# Sheet1.net
KiCad netlist of a schematic drawn in Altium Designer
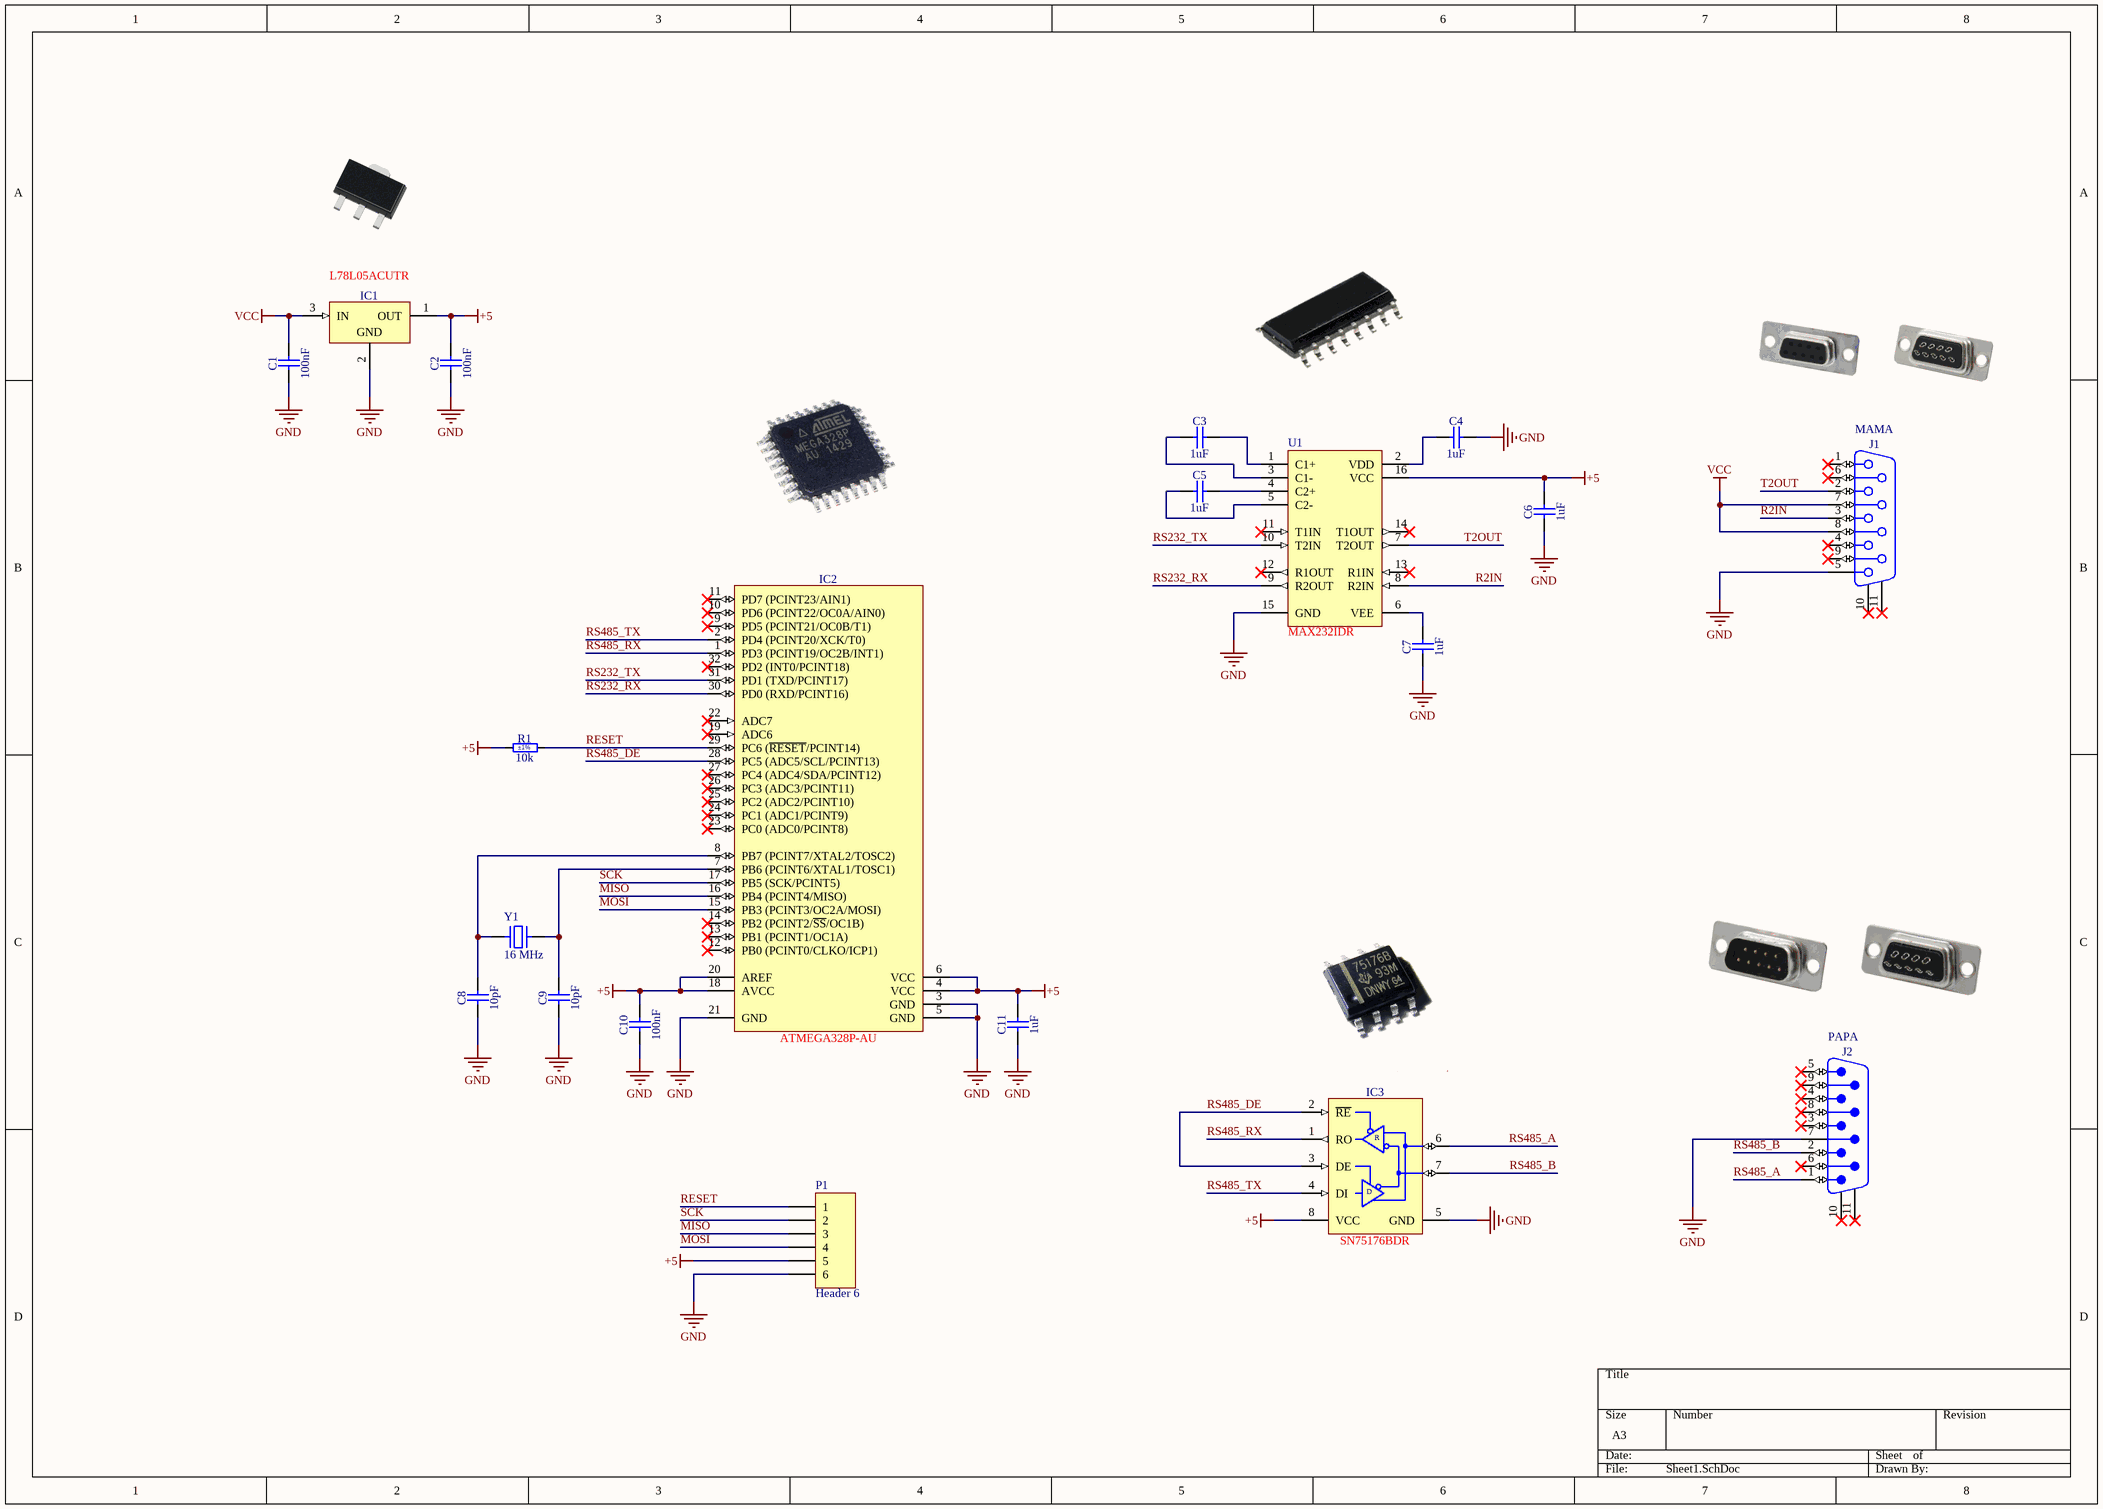
[diagram p0: Sheet1.SchDoc]

(export (version "E")
  (design (tool "Eeschema 10.0.6"))
  (components
    (comp (ref "C1")
      (value "100nF")
      (footprint "CAPC2012X135N")
      (description "Non-polarised capacitor")
      (fields
        (field (name "PART NUMBER") "CC0805_100NF_50V_10%_X7R")
        (field (name "VOLTAGE") "50V")
        (field (name "AUTHOR") "CERN DEM JLC")
      )
      (libsource (lib "Capacitors") (part "Capacitor - non polarized"))
    )
    (comp (ref "C2")
      (value "100nF")
      (footprint "CAPC2012X135N")
      (description "Non-polarised capacitor")
      (fields
        (field (name "PART NUMBER") "CC0805_100NF_50V_10%_X7R")
        (field (name "VOLTAGE") "50V")
        (field (name "AUTHOR") "CERN DEM JLC")
      )
      (libsource (lib "Capacitors") (part "Capacitor - non polarized"))
    )
    (comp (ref "C3")
      (value "1uF")
      (footprint "CAPC2012X140N")
      (description "Non-polarised capacitor")
      (fields
        (field (name "PART NUMBER") "CC0805_1UF_25V_10%_X7R")
        (field (name "VOLTAGE") "25V")
        (field (name "AUTHOR") "CERN DEM JLC")
      )
      (libsource (lib "Capacitors") (part "Capacitor - non polarized"))
    )
    (comp (ref "C4")
      (value "1uF")
      (footprint "CAPC2012X140N")
      (description "Non-polarised capacitor")
      (fields
        (field (name "PART NUMBER") "CC0805_1UF_25V_10%_X7R")
        (field (name "VOLTAGE") "25V")
        (field (name "AUTHOR") "CERN DEM JLC")
      )
      (libsource (lib "Capacitors") (part "Capacitor - non polarized"))
    )
    (comp (ref "C5")
      (value "1uF")
      (footprint "CAPC2012X140N")
      (description "Non-polarised capacitor")
      (fields
        (field (name "PART NUMBER") "CC0805_1UF_25V_10%_X7R")
        (field (name "VOLTAGE") "25V")
        (field (name "AUTHOR") "CERN DEM JLC")
      )
      (libsource (lib "Capacitors") (part "Capacitor - non polarized"))
    )
    (comp (ref "C6")
      (value "1uF")
      (footprint "CAPC2012X140N")
      (description "Non-polarised capacitor")
      (fields
        (field (name "PART NUMBER") "CC0805_1UF_25V_10%_X7R")
        (field (name "VOLTAGE") "25V")
        (field (name "AUTHOR") "CERN DEM JLC")
      )
      (libsource (lib "Capacitors") (part "Capacitor - non polarized"))
    )
    (comp (ref "C7")
      (value "1uF")
      (footprint "CAPC2012X140N")
      (description "Non-polarised capacitor")
      (fields
        (field (name "PART NUMBER") "CC0805_1UF_25V_10%_X7R")
        (field (name "VOLTAGE") "25V")
        (field (name "AUTHOR") "CERN DEM JLC")
      )
      (libsource (lib "Capacitors") (part "Capacitor - non polarized"))
    )
    (comp (ref "C8")
      (value "10pF")
      (footprint "CAPC2012X135N")
      (description "Non-polarised capacitor")
      (fields
        (field (name "PART NUMBER") "CC0805_10PF_50V_1%_NP0")
        (field (name "VOLTAGE") "50V")
        (field (name "AUTHOR") "CERN DEM MR")
      )
      (libsource (lib "Capacitors") (part "Capacitor - non polarized"))
    )
    (comp (ref "C9")
      (value "10pF")
      (footprint "CAPC2012X135N")
      (description "Non-polarised capacitor")
      (fields
        (field (name "PART NUMBER") "CC0805_10PF_50V_1%_NP0")
        (field (name "VOLTAGE") "50V")
        (field (name "AUTHOR") "CERN DEM MR")
      )
      (libsource (lib "Capacitors") (part "Capacitor - non polarized"))
    )
    (comp (ref "C10")
      (value "100nF")
      (footprint "CAPC2012X135N")
      (description "Non-polarised capacitor")
      (fields
        (field (name "PART NUMBER") "CC0805_100NF_50V_10%_X7R")
        (field (name "VOLTAGE") "50V")
        (field (name "AUTHOR") "CERN DEM JLC")
      )
      (libsource (lib "Capacitors") (part "Capacitor - non polarized"))
    )
    (comp (ref "C11")
      (value "1uF")
      (footprint "CAPC2012X140N")
      (description "Non-polarised capacitor")
      (fields
        (field (name "PART NUMBER") "CC0805_1UF_25V_10%_X7R")
        (field (name "VOLTAGE") "25V")
        (field (name "AUTHOR") "CERN DEM JLC")
      )
      (libsource (lib "Capacitors") (part "Capacitor - non polarized"))
    )
    (comp (ref "IC1")
      (value "L78L05ACUTR")
      (footprint "SOT89")
      (fields (field (name "MANUFACTURER") "ST MICROELECTRONICS") (field (name "AUTHOR") "CERN DEM JLC"))
      (libsource (lib "ICs And Semiconductors") (part "REG3 1OUT-2GND-3IN"))
    )
    (comp (ref "IC2")
      (value "ATMEGA328P-AU")
      (footprint "QFP80P900X900X120-32N")
      (description "8-bit AVR Microcontroller, 32KB Flash, 1KB EEPROM, 2KB SRAM, 32-Pin TQFP")
      (fields (field (name "MANUFACTURER") "ATMEL") (field (name "AUTHOR") "CERN DEM JLC"))
      (libsource (lib "ICs And Semiconductors") (part "ATMEGA328P-AU"))
    )
    (comp (ref "IC3")
      (value "SN75176BDR")
      (footprint "SOIC127P600X175-8N")
      (description "transceiver 4.75V~5.25V 1/1 SOIC-8_150mil RS-485/RS-422 ICs ROHS")
      (fields (field (name "AUTHOR") "CERN DEM JLC"))
      (libsource (lib "ICs And Semiconductors") (part "MAX3485"))
    )
    (comp (ref "J1")
      (value "D-Sub 9F")
      (footprint "D-Sub-9-pin:D-Sub")
      (description "Connector D-sub 9 Female")
      (fields
        (field (name "PART NUMBER") "HARTING_09 67 009 4754")
        (field (name "MANUFACTURER") "HARTING")
        (field (name "AUTHOR") "CERN DEM BC")
      )
      (libsource (lib "Connectors") (part "Connector D-sub 9 Female"))
    )
    (comp (ref "J2")
      (value "D-Sub 9M")
      (footprint "D-Sub-9-pin:D-Sub")
      (description "Connector D-sub 9 Male")
      (fields
        (field (name "PART NUMBER") "HARTING_09 66 162 6817")
        (field (name "MANUFACTURER") "HARTING")
        (field (name "AUTHOR") "CERN DEM HF")
      )
      (libsource (lib "Connectors") (part "Connector D-sub 9 Male"))
    )
    (comp (ref "P1")
      (value "Header 6")
      (footprint "HDR1X6")
      (description "Header, 6-Pin")
      (fields (field (name "PUBLISHER") "Altium Limited"))
      (libsource (lib "Miscellaneous Connectors") (part "Header 6"))
    )
    (comp (ref "R1")
      (value "10k")
      (footprint "RESC2012X60N")
      (description "Resistor - 1%")
      (fields
        (field (name "TOLERANCE") "±1%")
        (field (name "PART NUMBER") "R0805_10K_1%_0.125W_100PPM")
        (field (name "POWER") "0.125W")
        (field (name "AUTHOR") "CERN DEM JLC")
      )
      (libsource (lib "Resistors") (part "Resistor - 1%"))
    )
    (comp (ref "U1")
      (value "MAX232IDR")
      (footprint "SOIC-16 9.9X3.9MM P1.27MM")
      (description "120Kbps 4.5V~5.5V transceiver 2/2 SOIC-16 RS232 ICs ROHS")
      (libsource (lib "Chip") (part "MAX232 (SMD)"))
    )
    (comp (ref "Y1")
      (value "16 MHz")
      (footprint "NDK NX5032GA")
      (description "CRYSTAL 16.0000MHZ 8PF SMD")
      (fields
        (field (name "PART NUMBER") "NX5032GA-16MHZ-STD-CSK-4")
        (field (name "MANUFACTURER") "NDK America, Inc.")
      )
      (libsource (lib "altium_library") (part "NDK Crystal NX5032GA"))
    )
  )
  (nets
    (net (code "1") (name "+5") (class "Default")
      (node (ref "C10") (pin "2") (pinfunction "2_2") (pintype "passive"))
      (node (ref "C11") (pin "2") (pinfunction "2_2") (pintype "passive"))
      (node (ref "C2") (pin "2") (pinfunction "2_2") (pintype "passive"))
      (node (ref "C6") (pin "2") (pinfunction "2_2") (pintype "passive"))
      (node (ref "IC1") (pin "1") (pinfunction "OUT_1") (pintype "power_in"))
      (node (ref "IC2") (pin "18") (pinfunction "AVCC_18") (pintype "power_in"))
      (node (ref "IC2") (pin "20") (pinfunction "AREF_20") (pintype "passive"))
      (node (ref "IC2") (pin "4") (pinfunction "VCC_4") (pintype "power_in"))
      (node (ref "IC2") (pin "6") (pinfunction "VCC_6") (pintype "power_in"))
      (node (ref "IC3") (pin "8") (pinfunction "VCC_8") (pintype "power_in"))
      (node (ref "P1") (pin "5") (pinfunction "5_5") (pintype "passive"))
      (node (ref "R1") (pin "1") (pinfunction "1_1") (pintype "passive"))
      (node (ref "U1") (pin "16") (pinfunction "VCC_16") (pintype "power_in"))
    )
    (net (code "2") (name "/MISO") (class "Default")
      (node (ref "IC2") (pin "16") (pinfunction "PB4_(PCINT4/MISO)_16") (pintype "bidirectional"))
      (node (ref "P1") (pin "3") (pinfunction "3_3") (pintype "passive"))
    )
    (net (code "3") (name "/MOSI") (class "Default")
      (node (ref "IC2") (pin "15") (pinfunction "PB3_(PCINT3/OC2A/MOSI)_15") (pintype "bidirectional"))
      (node (ref "P1") (pin "4") (pinfunction "4_4") (pintype "passive"))
    )
    (net (code "4") (name "/R2IN") (class "Default")
      (node (ref "J1") (pin "3") (pinfunction "3_3") (pintype "bidirectional"))
      (node (ref "U1") (pin "8") (pinfunction "R2IN_8") (pintype "input"))
    )
    (net (code "5") (name "/RESET") (class "Default")
      (node (ref "IC2") (pin "29") (pinfunction "PC6_(~{RESET}/PCINT14)_29") (pintype "bidirectional"))
      (node (ref "P1") (pin "1") (pinfunction "1_1") (pintype "passive"))
      (node (ref "R1") (pin "2") (pinfunction "2_2") (pintype "passive"))
    )
    (net (code "6") (name "/RS232_RX") (class "Default")
      (node (ref "IC2") (pin "30") (pinfunction "PD0_(RXD/PCINT16)_30") (pintype "bidirectional"))
      (node (ref "U1") (pin "9") (pinfunction "R2OUT_9") (pintype "output"))
    )
    (net (code "7") (name "/RS232_TX") (class "Default")
      (node (ref "IC2") (pin "31") (pinfunction "PD1_(TXD/PCINT17)_31") (pintype "bidirectional"))
      (node (ref "U1") (pin "10") (pinfunction "T2IN_10") (pintype "input"))
    )
    (net (code "8") (name "/RS485_A") (class "Default")
      (node (ref "IC3") (pin "6") (pinfunction "A_6") (pintype "bidirectional"))
      (node (ref "J2") (pin "1") (pinfunction "1_1") (pintype "bidirectional"))
    )
    (net (code "9") (name "/RS485_B") (class "Default")
      (node (ref "IC3") (pin "7") (pinfunction "B_7") (pintype "bidirectional"))
      (node (ref "J2") (pin "2") (pinfunction "2_2") (pintype "bidirectional"))
    )
    (net (code "10") (name "/RS485_DE") (class "Default")
      (node (ref "IC2") (pin "28") (pinfunction "PC5_(ADC5/SCL/PCINT13)_28") (pintype "bidirectional"))
      (node (ref "IC3") (pin "2") (pinfunction "~{RE}_2") (pintype "input"))
      (node (ref "IC3") (pin "3") (pinfunction "DE_3") (pintype "input"))
    )
    (net (code "11") (name "/RS485_RX") (class "Default")
      (node (ref "IC2") (pin "1") (pinfunction "PD3_(PCINT19/OC2B/INT1)_1") (pintype "bidirectional"))
      (node (ref "IC3") (pin "1") (pinfunction "RO_1") (pintype "output"))
    )
    (net (code "12") (name "/RS485_TX") (class "Default")
      (node (ref "IC2") (pin "2") (pinfunction "PD4_(PCINT20/XCK/T0)_2") (pintype "bidirectional"))
      (node (ref "IC3") (pin "4") (pinfunction "DI_4") (pintype "input"))
    )
    (net (code "13") (name "/SCK") (class "Default")
      (node (ref "IC2") (pin "17") (pinfunction "PB5_(SCK/PCINT5)_17") (pintype "bidirectional"))
      (node (ref "P1") (pin "2") (pinfunction "2_2") (pintype "passive"))
    )
    (net (code "14") (name "/T2OUT") (class "Default")
      (node (ref "J1") (pin "2") (pinfunction "2_2") (pintype "bidirectional"))
      (node (ref "U1") (pin "7") (pinfunction "T2OUT_7") (pintype "output"))
    )
    (net (code "15") (name "GND") (class "Default")
      (node (ref "C1") (pin "1") (pinfunction "1_1") (pintype "passive"))
      (node (ref "C10") (pin "1") (pinfunction "1_1") (pintype "passive"))
      (node (ref "C11") (pin "1") (pinfunction "1_1") (pintype "passive"))
      (node (ref "C2") (pin "1") (pinfunction "1_1") (pintype "passive"))
      (node (ref "C4") (pin "2") (pinfunction "2_2") (pintype "passive"))
      (node (ref "C6") (pin "1") (pinfunction "1_1") (pintype "passive"))
      (node (ref "C7") (pin "1") (pinfunction "1_1") (pintype "passive"))
      (node (ref "C8") (pin "1") (pinfunction "1_1") (pintype "passive"))
      (node (ref "C9") (pin "1") (pinfunction "1_1") (pintype "passive"))
      (node (ref "IC1") (pin "2") (pinfunction "GND_2") (pintype "power_in"))
      (node (ref "IC2") (pin "21") (pinfunction "GND_21") (pintype "power_in"))
      (node (ref "IC2") (pin "3") (pinfunction "GND_3") (pintype "power_in"))
      (node (ref "IC2") (pin "5") (pinfunction "GND_5") (pintype "power_in"))
      (node (ref "IC3") (pin "5") (pinfunction "GND_5") (pintype "power_in"))
      (node (ref "J1") (pin "5") (pinfunction "5_5") (pintype "power_in"))
      (node (ref "J2") (pin "7") (pinfunction "7_7") (pintype "passive"))
      (node (ref "P1") (pin "6") (pinfunction "6_6") (pintype "passive"))
      (node (ref "U1") (pin "15") (pinfunction "GND_15") (pintype "power_in"))
    )
    (net (code "16") (name "Net-(IC2-PB6_(PCINT6{slash}XTAL1{slash}TOSC1))") (class "Default")
      (node (ref "C9") (pin "2") (pinfunction "2_2") (pintype "passive"))
      (node (ref "IC2") (pin "7") (pinfunction "PB6_(PCINT6/XTAL1/TOSC1)_7") (pintype "bidirectional"))
      (node (ref "Y1") (pin "1") (pinfunction "1_1") (pintype "passive"))
    )
    (net (code "17") (name "Net-(IC2-PB7_(PCINT7{slash}XTAL2{slash}TOSC2))") (class "Default")
      (node (ref "C8") (pin "2") (pinfunction "2_2") (pintype "passive"))
      (node (ref "IC2") (pin "8") (pinfunction "PB7_(PCINT7/XTAL2/TOSC2)_8") (pintype "bidirectional"))
      (node (ref "Y1") (pin "2") (pinfunction "2_2") (pintype "passive"))
    )
    (net (code "18") (name "Net-(U1-C1+)") (class "Default")
      (node (ref "C3") (pin "2") (pinfunction "2_2") (pintype "passive"))
      (node (ref "U1") (pin "1") (pinfunction "C1+_1") (pintype "passive"))
    )
    (net (code "19") (name "Net-(U1-C1-)") (class "Default")
      (node (ref "C3") (pin "1") (pinfunction "1_1") (pintype "passive"))
      (node (ref "U1") (pin "3") (pinfunction "C1-_3") (pintype "passive"))
    )
    (net (code "20") (name "Net-(U1-C2+)") (class "Default")
      (node (ref "C5") (pin "2") (pinfunction "2_2") (pintype "passive"))
      (node (ref "U1") (pin "4") (pinfunction "C2+_4") (pintype "passive"))
    )
    (net (code "21") (name "Net-(U1-C2-)") (class "Default")
      (node (ref "C5") (pin "1") (pinfunction "1_1") (pintype "passive"))
      (node (ref "U1") (pin "5") (pinfunction "C2-_5") (pintype "passive"))
    )
    (net (code "22") (name "Net-(U1-VDD)") (class "Default")
      (node (ref "C4") (pin "1") (pinfunction "1_1") (pintype "passive"))
      (node (ref "U1") (pin "2") (pinfunction "VDD_2") (pintype "power_in"))
    )
    (net (code "23") (name "Net-(U1-VEE)") (class "Default")
      (node (ref "C7") (pin "2") (pinfunction "2_2") (pintype "passive"))
      (node (ref "U1") (pin "6") (pinfunction "VEE_6") (pintype "power_in"))
    )
    (net (code "24") (name "VCC") (class "Default")
      (node (ref "C1") (pin "2") (pinfunction "2_2") (pintype "passive"))
      (node (ref "IC1") (pin "3") (pinfunction "IN_3") (pintype "input"))
      (node (ref "J1") (pin "7") (pinfunction "7_7") (pintype "bidirectional"))
      (node (ref "J1") (pin "8") (pinfunction "8_8") (pintype "bidirectional"))
    )
    (net (code "25") (name "unconnected-(IC2-ADC6-Pad19)") (class "Default")
      (node (ref "IC2") (pin "19") (pinfunction "ADC6_19") (pintype "input+no_connect"))
    )
    (net (code "26") (name "unconnected-(IC2-ADC7-Pad22)") (class "Default")
      (node (ref "IC2") (pin "22") (pinfunction "ADC7_22") (pintype "input+no_connect"))
    )
    (net (code "27") (name "unconnected-(IC2-PB0_(PCINT0{slash}CLKO{slash}ICP1)-Pad12)") (class "Default")
      (node (ref "IC2") (pin "12") (pinfunction "PB0_(PCINT0/CLKO/ICP1)_12") (pintype "bidirectional+no_connect"))
    )
    (net (code "28") (name "unconnected-(IC2-PB1_(PCINT1{slash}OC1A)-Pad13)") (class "Default")
      (node (ref "IC2") (pin "13") (pinfunction "PB1_(PCINT1/OC1A)_13") (pintype "bidirectional+no_connect"))
    )
    (net (code "29") (name "unconnected-(IC2-PB2_(PCINT2{slash}~{SS}{slash}OC1B)-Pad14)") (class "Default")
      (node (ref "IC2") (pin "14") (pinfunction "PB2_(PCINT2/~{SS}/OC1B)_14") (pintype "bidirectional+no_connect"))
    )
    (net (code "30") (name "unconnected-(IC2-PC0_(ADC0{slash}PCINT8)-Pad23)") (class "Default")
      (node (ref "IC2") (pin "23") (pinfunction "PC0_(ADC0/PCINT8)_23") (pintype "bidirectional+no_connect"))
    )
    (net (code "31") (name "unconnected-(IC2-PC1_(ADC1{slash}PCINT9)-Pad24)") (class "Default")
      (node (ref "IC2") (pin "24") (pinfunction "PC1_(ADC1/PCINT9)_24") (pintype "bidirectional+no_connect"))
    )
    (net (code "32") (name "unconnected-(IC2-PC2_(ADC2{slash}PCINT10)-Pad25)") (class "Default")
      (node (ref "IC2") (pin "25") (pinfunction "PC2_(ADC2/PCINT10)_25") (pintype "bidirectional+no_connect"))
    )
    (net (code "33") (name "unconnected-(IC2-PC3_(ADC3{slash}PCINT11)-Pad26)") (class "Default")
      (node (ref "IC2") (pin "26") (pinfunction "PC3_(ADC3/PCINT11)_26") (pintype "bidirectional+no_connect"))
    )
    (net (code "34") (name "unconnected-(IC2-PC4_(ADC4{slash}SDA{slash}PCINT12)-Pad27)") (class "Default")
      (node (ref "IC2") (pin "27") (pinfunction "PC4_(ADC4/SDA/PCINT12)_27") (pintype "bidirectional+no_connect"))
    )
    (net (code "35") (name "unconnected-(IC2-PD2_(INT0{slash}PCINT18)-Pad32)") (class "Default")
      (node (ref "IC2") (pin "32") (pinfunction "PD2_(INT0/PCINT18)_32") (pintype "bidirectional+no_connect"))
    )
    (net (code "36") (name "unconnected-(IC2-PD5_(PCINT21{slash}OC0B{slash}T1)-Pad9)") (class "Default")
      (node (ref "IC2") (pin "9") (pinfunction "PD5_(PCINT21/OC0B/T1)_9") (pintype "bidirectional+no_connect"))
    )
    (net (code "37") (name "unconnected-(IC2-PD6_(PCINT22{slash}OC0A{slash}AIN0)-Pad10)") (class "Default")
      (node (ref "IC2") (pin "10") (pinfunction "PD6_(PCINT22/OC0A/AIN0)_10") (pintype "bidirectional+no_connect"))
    )
    (net (code "38") (name "unconnected-(IC2-PD7_(PCINT23{slash}AIN1)-Pad11)") (class "Default")
      (node (ref "IC2") (pin "11") (pinfunction "PD7_(PCINT23/AIN1)_11") (pintype "bidirectional+no_connect"))
    )
    (net (code "39") (name "unconnected-(J1-Pad1)") (class "Default")
      (node (ref "J1") (pin "1") (pinfunction "1_1") (pintype "bidirectional+no_connect"))
    )
    (net (code "40") (name "unconnected-(J1-Pad4)") (class "Default")
      (node (ref "J1") (pin "4") (pinfunction "4_4") (pintype "bidirectional+no_connect"))
    )
    (net (code "41") (name "unconnected-(J1-Pad6)") (class "Default")
      (node (ref "J1") (pin "6") (pinfunction "6_6") (pintype "bidirectional+no_connect"))
    )
    (net (code "42") (name "unconnected-(J1-Pad9)") (class "Default")
      (node (ref "J1") (pin "9") (pinfunction "9_9") (pintype "bidirectional+no_connect"))
    )
    (net (code "43") (name "unconnected-(J1-Pad10)") (class "Default")
      (node (ref "J1") (pin "10") (pinfunction "10_10") (pintype "passive+no_connect"))
    )
    (net (code "44") (name "unconnected-(J1-Pad11)") (class "Default")
      (node (ref "J1") (pin "11") (pinfunction "11_11") (pintype "passive+no_connect"))
    )
    (net (code "45") (name "unconnected-(J2-Pad3)") (class "Default")
      (node (ref "J2") (pin "3") (pinfunction "3_3") (pintype "bidirectional+no_connect"))
    )
    (net (code "46") (name "unconnected-(J2-Pad4)") (class "Default")
      (node (ref "J2") (pin "4") (pinfunction "4_4") (pintype "bidirectional+no_connect"))
    )
    (net (code "47") (name "unconnected-(J2-Pad5)") (class "Default")
      (node (ref "J2") (pin "5") (pinfunction "5_5") (pintype "bidirectional+no_connect"))
    )
    (net (code "48") (name "unconnected-(J2-Pad6)") (class "Default")
      (node (ref "J2") (pin "6") (pinfunction "6_6") (pintype "bidirectional+no_connect"))
    )
    (net (code "49") (name "unconnected-(J2-Pad8)") (class "Default")
      (node (ref "J2") (pin "8") (pinfunction "8_8") (pintype "bidirectional+no_connect"))
    )
    (net (code "50") (name "unconnected-(J2-Pad9)") (class "Default")
      (node (ref "J2") (pin "9") (pinfunction "9_9") (pintype "bidirectional+no_connect"))
    )
    (net (code "51") (name "unconnected-(J2-Pad10)") (class "Default")
      (node (ref "J2") (pin "10") (pinfunction "10_10") (pintype "passive+no_connect"))
    )
    (net (code "52") (name "unconnected-(J2-Pad11)") (class "Default")
      (node (ref "J2") (pin "11") (pinfunction "11_11") (pintype "passive+no_connect"))
    )
    (net (code "53") (name "unconnected-(U1-R1IN-Pad13)") (class "Default")
      (node (ref "U1") (pin "13") (pinfunction "R1IN_13") (pintype "input+no_connect"))
    )
    (net (code "54") (name "unconnected-(U1-R1OUT-Pad12)") (class "Default")
      (node (ref "U1") (pin "12") (pinfunction "R1OUT_12") (pintype "output+no_connect"))
    )
    (net (code "55") (name "unconnected-(U1-T1IN-Pad11)") (class "Default")
      (node (ref "U1") (pin "11") (pinfunction "T1IN_11") (pintype "input+no_connect"))
    )
    (net (code "56") (name "unconnected-(U1-T1OUT-Pad14)") (class "Default")
      (node (ref "U1") (pin "14") (pinfunction "T1OUT_14") (pintype "output+no_connect"))
    )
  )
)
